# Baos_Board.net
KiCad netlist of a schematic drawn in EAGLE
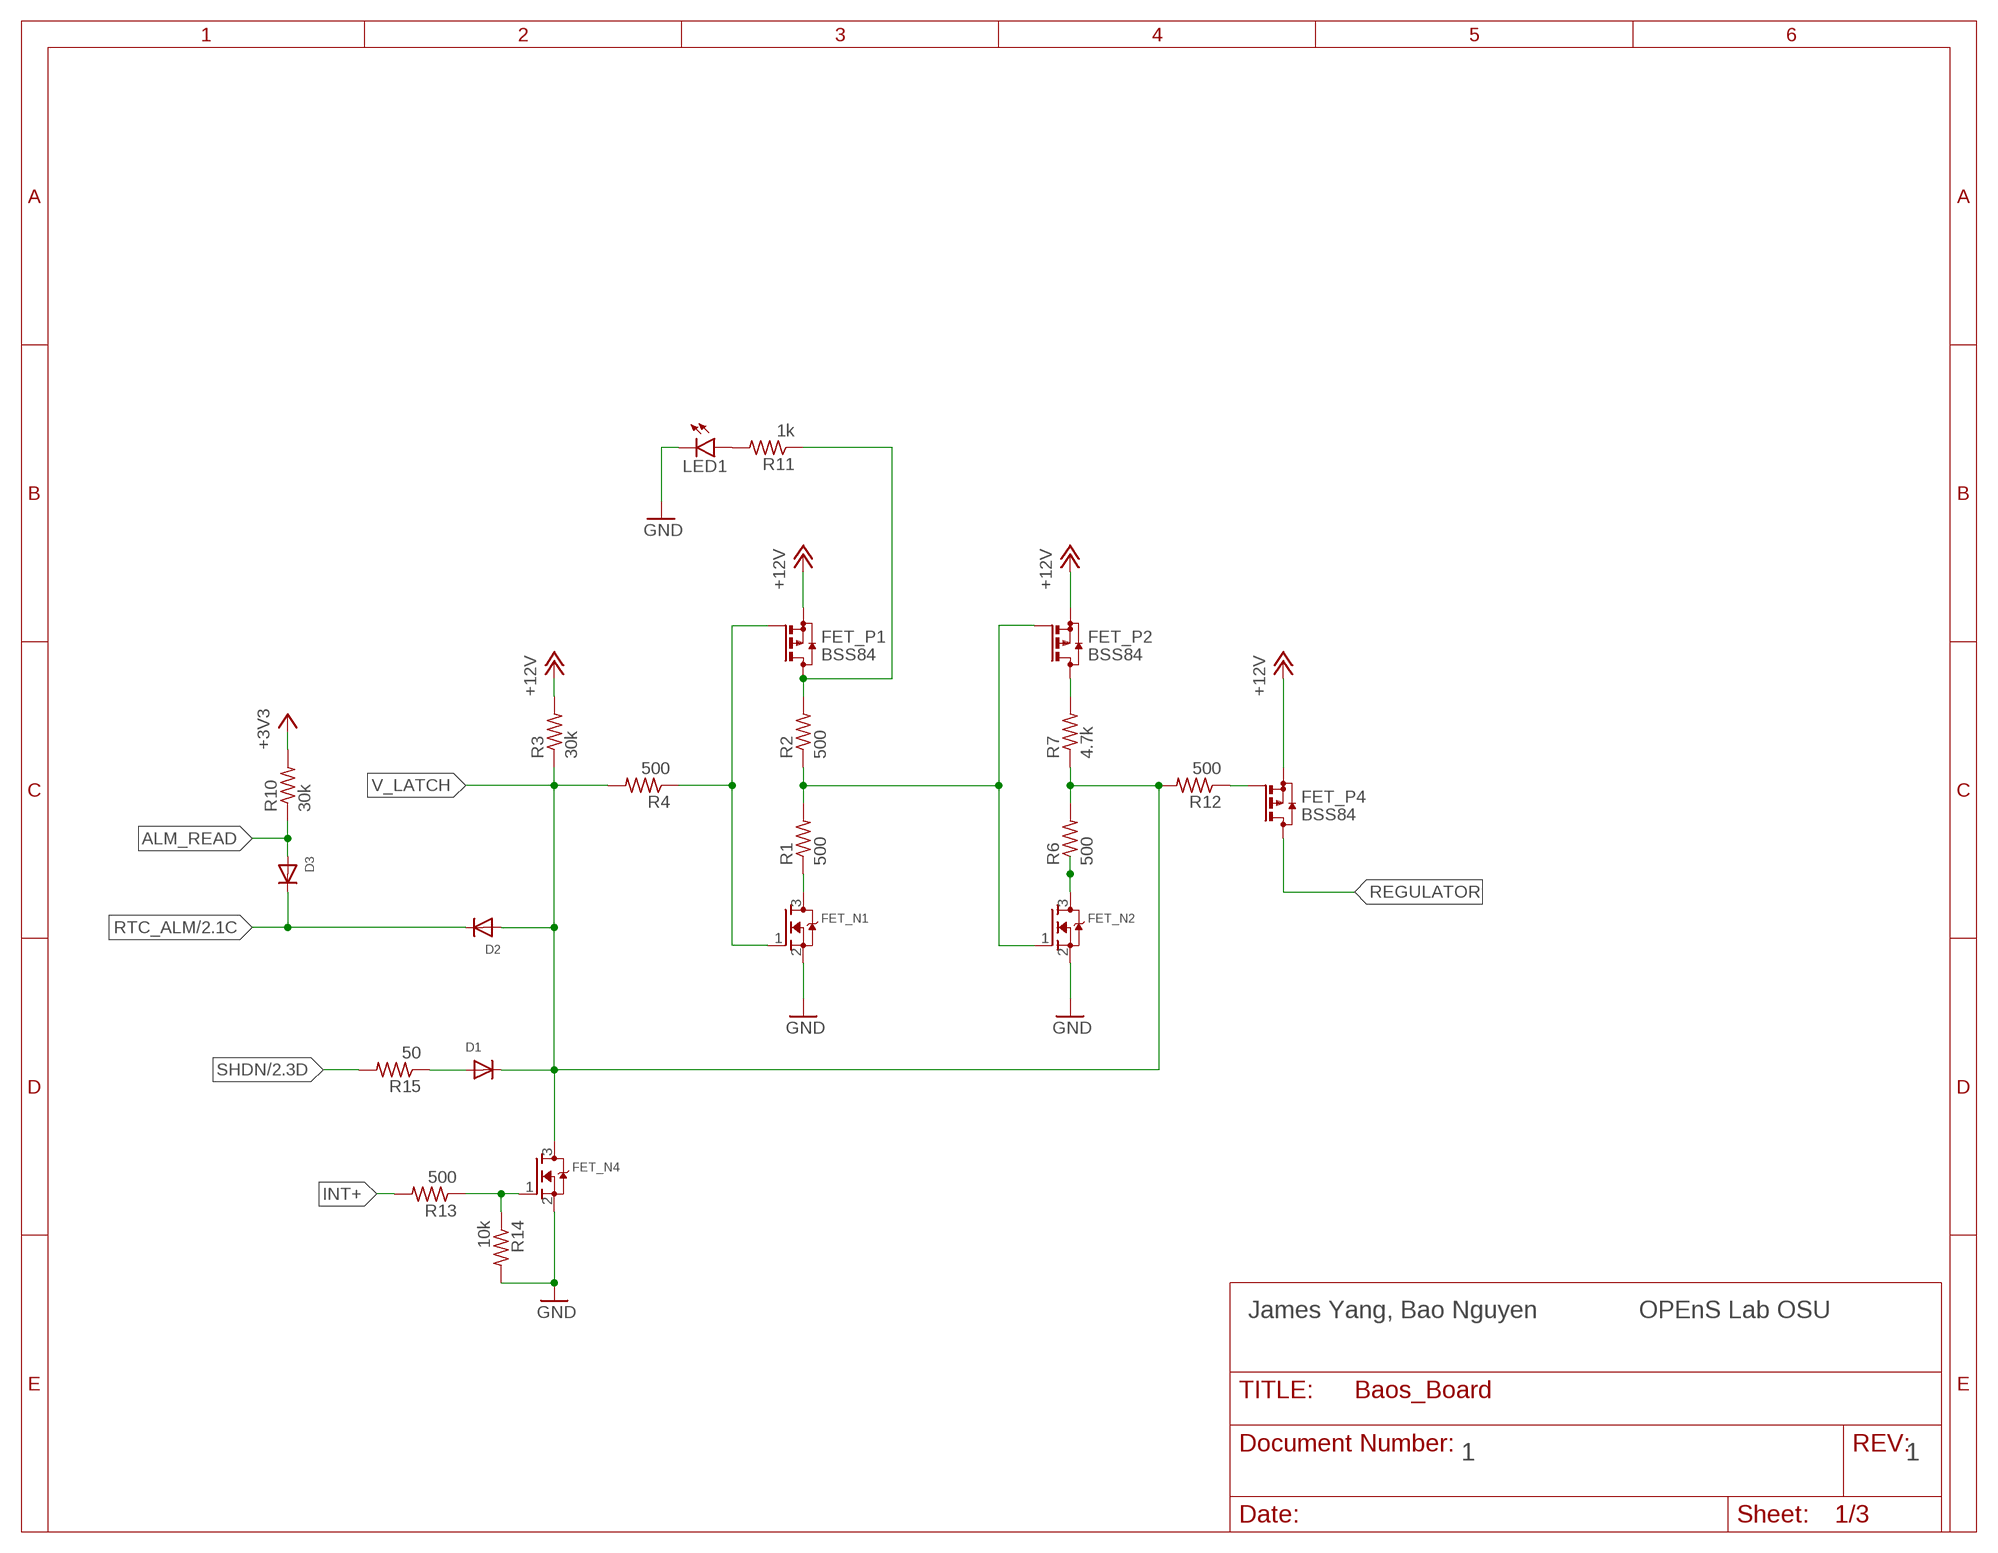
[diagram p0: schematic, sheet 1]
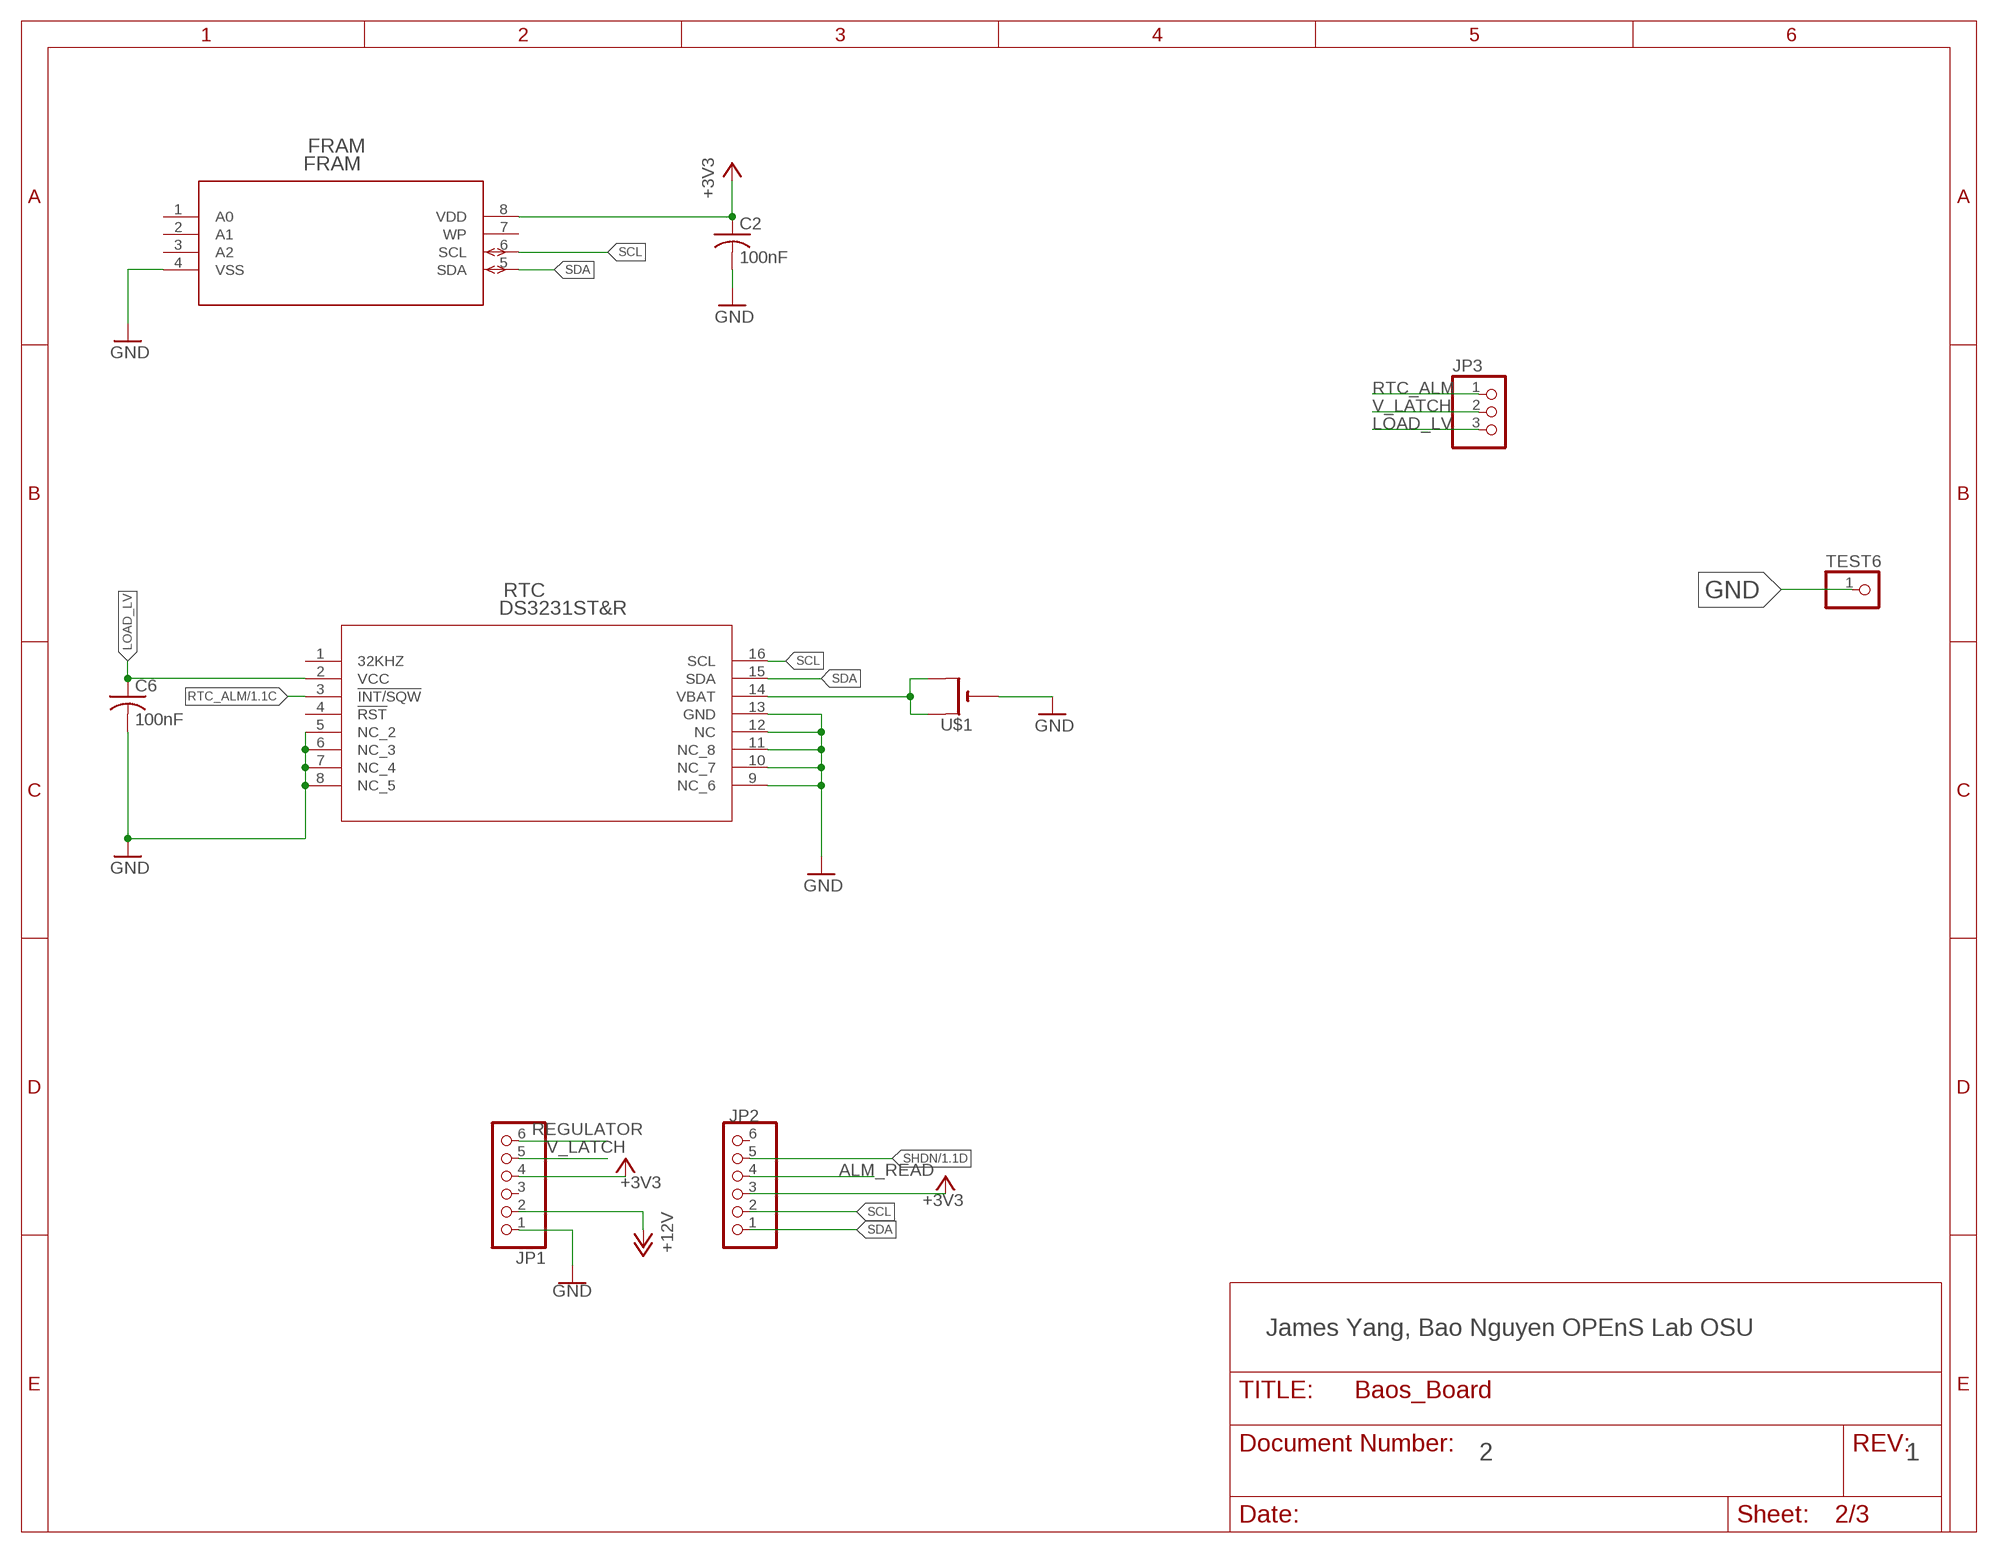
[diagram p1: schematic, sheet 2]

(export (version "E")
  (design (tool "Eeschema 10.0.6"))
  (components
    (comp (ref "D1")
      (value "DIODESOD-123")
      (footprint "eagle-import:SOD-123")
      (libsource (lib "eagle-import") (part "DIODESOD-123"))
    )
    (comp (ref "D2")
      (value "DIODESOD-123")
      (footprint "eagle-import:SOD-123")
      (libsource (lib "eagle-import") (part "DIODESOD-123"))
    )
    (comp (ref "D3")
      (value "DIODESOD-123")
      (footprint "eagle-import:SOD-123")
      (libsource (lib "eagle-import") (part "DIODESOD-123"))
    )
    (comp (ref "FET_N1")
      (value "MOSFET-NREFLOW")
      (footprint "eagle-import:SOT23")
      (libsource (lib "eagle-import") (part "MOSFET-NREFLOW"))
    )
    (comp (ref "FET_N2")
      (value "MOSFET-NREFLOW")
      (footprint "eagle-import:SOT23")
      (libsource (lib "eagle-import") (part "MOSFET-NREFLOW"))
    )
    (comp (ref "FET_N4")
      (value "MOSFET-NREFLOW")
      (footprint "eagle-import:SOT23")
      (libsource (lib "eagle-import") (part "MOSFET-NREFLOW"))
    )
    (comp (ref "FET_P1")
      (value "BSS84")
      (footprint "eagle-import:SOT23")
      (libsource (lib "eagle-import") (part "BSS84"))
    )
    (comp (ref "FET_P2")
      (value "BSS84")
      (footprint "eagle-import:SOT23")
      (libsource (lib "eagle-import") (part "BSS84"))
    )
    (comp (ref "FET_P4")
      (value "BSS84")
      (footprint "eagle-import:SOT23")
      (libsource (lib "eagle-import") (part "BSS84"))
    )
    (comp (ref "LED1")
      (value "LEDSMT1206")
      (footprint "eagle-import:1206")
      (libsource (lib "eagle-import") (part "LEDSMT1206"))
    )
    (comp (ref "R1")
      (value "500")
      (footprint "eagle-import:R0805")
      (libsource (lib "eagle-import") (part "R-US_R0805"))
    )
    (comp (ref "R2")
      (value "500")
      (footprint "eagle-import:R0805")
      (libsource (lib "eagle-import") (part "R-US_R0805"))
    )
    (comp (ref "R3")
      (value "30k")
      (footprint "eagle-import:R0805")
      (libsource (lib "eagle-import") (part "R-US_R0805"))
    )
    (comp (ref "R4")
      (value "500")
      (footprint "eagle-import:R0805")
      (libsource (lib "eagle-import") (part "R-US_R0805"))
    )
    (comp (ref "R6")
      (value "500")
      (footprint "eagle-import:R0805")
      (libsource (lib "eagle-import") (part "R-US_R0805"))
    )
    (comp (ref "R7")
      (value "4.7k")
      (footprint "eagle-import:R0805")
      (libsource (lib "eagle-import") (part "R-US_R0805"))
    )
    (comp (ref "R10")
      (value "30k")
      (footprint "eagle-import:R0805")
      (libsource (lib "eagle-import") (part "R-US_R0805"))
    )
    (comp (ref "R11")
      (value "1k")
      (footprint "eagle-import:R0805")
      (libsource (lib "eagle-import") (part "R-US_R0805"))
    )
    (comp (ref "R12")
      (value "500")
      (footprint "eagle-import:R0805")
      (libsource (lib "eagle-import") (part "R-US_R0805"))
    )
    (comp (ref "R13")
      (value "500")
      (footprint "eagle-import:R0805")
      (libsource (lib "eagle-import") (part "R-US_R0805"))
    )
    (comp (ref "R14")
      (value "10k")
      (footprint "eagle-import:R0805")
      (libsource (lib "eagle-import") (part "R-US_R0805"))
    )
    (comp (ref "R15")
      (value "50")
      (footprint "eagle-import:R0805")
      (libsource (lib "eagle-import") (part "R-US_R0805"))
    )
    (comp (ref "C2")
      (value "100nF")
      (footprint "eagle-import:C0805")
      (libsource (lib "eagle-import") (part "C-USC0805"))
    )
    (comp (ref "C6")
      (value "100nF")
      (footprint "eagle-import:C0805")
      (libsource (lib "eagle-import") (part "C-USC0805"))
    )
    (comp (ref "FRAM")
      (value "FRAM")
      (footprint "eagle-import:FPT-8P-M02")
      (fields (field (name "MANUFACTURER_PART_NUMBER") "Inc."))
      (libsource (lib "eagle-import") (part "FRAM"))
    )
    (comp (ref "JP1")
      (value "PINHD-1X6")
      (footprint "eagle-import:1X06")
      (libsource (lib "eagle-import") (part "PINHD-1X6"))
    )
    (comp (ref "JP2")
      (value "PINHD-1X6")
      (footprint "eagle-import:1X06")
      (libsource (lib "eagle-import") (part "PINHD-1X6"))
    )
    (comp (ref "JP3")
      (value "PINHD-1X3")
      (footprint "eagle-import:1X03")
      (libsource (lib "eagle-import") (part "PINHD-1X3"))
    )
    (comp (ref "RTC")
      (value "DS3231ST&R")
      (footprint "eagle-import:21-0042B_16")
      (fields (field (name "MANUFACTURER_PART_NUMBER") "DS3231S#T&R"))
      (libsource (lib "eagle-import") (part "DS3231ST&R"))
    )
    (comp (ref "TEST6")
      (value "PINHD-1X1")
      (footprint "eagle-import:1X01")
      (libsource (lib "eagle-import") (part "PINHD-1X1"))
    )
    (comp (ref "U$1")
      (value "CR1220SMT")
      (footprint "eagle-import:CR1220-SMD")
      (libsource (lib "eagle-import") (part "CR1220SMT"))
    )
  )
  (nets
    (net (code "1") (name "+3V3") (class "Default")
      (node (ref "C2") (pin "1") (pinfunction "1_1") (pintype "passive"))
      (node (ref "FRAM") (pin "8") (pinfunction "VDD_8") (pintype "power_in"))
      (node (ref "JP1") (pin "4") (pinfunction "4_4") (pintype "passive"))
      (node (ref "JP2") (pin "3") (pinfunction "3_3") (pintype "passive"))
      (node (ref "R10") (pin "2") (pinfunction "2_2") (pintype "passive"))
    )
    (net (code "2") (name "+12V") (class "Default")
      (node (ref "FET_P1") (pin "2") (pinfunction "S_2") (pintype "passive"))
      (node (ref "FET_P2") (pin "2") (pinfunction "S_2") (pintype "passive"))
      (node (ref "FET_P4") (pin "2") (pinfunction "S_2") (pintype "passive"))
      (node (ref "JP1") (pin "2") (pinfunction "2_2") (pintype "passive"))
      (node (ref "R3") (pin "2") (pinfunction "2_2") (pintype "passive"))
    )
    (net (code "3") (name "ALM_READ") (class "Default")
      (node (ref "D3") (pin "A") (pinfunction "A_A") (pintype "passive"))
      (node (ref "JP2") (pin "4") (pinfunction "4_4") (pintype "passive"))
      (node (ref "R10") (pin "1") (pinfunction "1_1") (pintype "passive"))
    )
    (net (code "4") (name "GND") (class "Default")
      (node (ref "C2") (pin "2") (pinfunction "2_2") (pintype "passive"))
      (node (ref "C6") (pin "2") (pinfunction "2_2") (pintype "passive"))
      (node (ref "FET_N1") (pin "2") (pinfunction "S_2") (pintype "bidirectional"))
      (node (ref "FET_N2") (pin "2") (pinfunction "S_2") (pintype "bidirectional"))
      (node (ref "FET_N4") (pin "2") (pinfunction "S_2") (pintype "bidirectional"))
      (node (ref "FRAM") (pin "4") (pinfunction "VSS_4") (pintype "power_in"))
      (node (ref "JP1") (pin "1") (pinfunction "1_1") (pintype "passive"))
      (node (ref "LED1") (pin "C") (pinfunction "C_C") (pintype "passive"))
      (node (ref "R14") (pin "2") (pinfunction "2_2") (pintype "passive"))
      (node (ref "RTC") (pin "10") (pinfunction "NC_7_10") (pintype "passive"))
      (node (ref "RTC") (pin "11") (pinfunction "NC_8_11") (pintype "passive"))
      (node (ref "RTC") (pin "12") (pinfunction "NC_12") (pintype "passive"))
      (node (ref "RTC") (pin "13") (pinfunction "GND_13") (pintype "power_in"))
      (node (ref "RTC") (pin "5") (pinfunction "NC_2_5") (pintype "passive"))
      (node (ref "RTC") (pin "6") (pinfunction "NC_3_6") (pintype "passive"))
      (node (ref "RTC") (pin "7") (pinfunction "NC_4_7") (pintype "passive"))
      (node (ref "RTC") (pin "8") (pinfunction "NC_5_8") (pintype "passive"))
      (node (ref "RTC") (pin "9") (pinfunction "NC_6_9") (pintype "passive"))
      (node (ref "TEST6") (pin "1") (pinfunction "1_1") (pintype "passive"))
      (node (ref "U$1") (pin "-") (pinfunction "-_-") (pintype "passive"))
    )
    (net (code "5") (name "INT+") (class "Default")
      (node (ref "R13") (pin "2") (pinfunction "2_2") (pintype "passive"))
    )
    (net (code "6") (name "LOAD_LV") (class "Default")
      (node (ref "C6") (pin "1") (pinfunction "1_1") (pintype "passive"))
      (node (ref "JP3") (pin "3") (pinfunction "3_3") (pintype "passive"))
      (node (ref "RTC") (pin "2") (pinfunction "VCC_2") (pintype "power_in"))
    )
    (net (code "7") (name "Net-(D1-PadA)") (class "Default")
      (node (ref "D1") (pin "A") (pinfunction "A_A") (pintype "passive"))
      (node (ref "R15") (pin "1") (pinfunction "1_1") (pintype "passive"))
    )
    (net (code "8") (name "Net-(FET_N1-D)") (class "Default")
      (node (ref "FET_N1") (pin "3") (pinfunction "D_3") (pintype "bidirectional"))
      (node (ref "R1") (pin "1") (pinfunction "1_1") (pintype "passive"))
    )
    (net (code "9") (name "Net-(FET_N1-G)") (class "Default")
      (node (ref "FET_N1") (pin "1") (pinfunction "G_1") (pintype "bidirectional"))
      (node (ref "FET_P1") (pin "1") (pinfunction "G_1") (pintype "passive"))
      (node (ref "R4") (pin "1") (pinfunction "1_1") (pintype "passive"))
    )
    (net (code "10") (name "Net-(FET_N2-D)") (class "Default")
      (node (ref "FET_N2") (pin "3") (pinfunction "D_3") (pintype "bidirectional"))
      (node (ref "R6") (pin "1") (pinfunction "1_1") (pintype "passive"))
    )
    (net (code "11") (name "Net-(FET_N2-G)") (class "Default")
      (node (ref "FET_N2") (pin "1") (pinfunction "G_1") (pintype "bidirectional"))
      (node (ref "FET_P2") (pin "1") (pinfunction "G_1") (pintype "passive"))
      (node (ref "R1") (pin "2") (pinfunction "2_2") (pintype "passive"))
      (node (ref "R2") (pin "1") (pinfunction "1_1") (pintype "passive"))
    )
    (net (code "12") (name "Net-(FET_N4-G)") (class "Default")
      (node (ref "FET_N4") (pin "1") (pinfunction "G_1") (pintype "bidirectional"))
      (node (ref "R13") (pin "1") (pinfunction "1_1") (pintype "passive"))
      (node (ref "R14") (pin "1") (pinfunction "1_1") (pintype "passive"))
    )
    (net (code "13") (name "Net-(FET_P1-D)") (class "Default")
      (node (ref "FET_P1") (pin "3") (pinfunction "D_3") (pintype "passive"))
      (node (ref "R11") (pin "1") (pinfunction "1_1") (pintype "passive"))
      (node (ref "R2") (pin "2") (pinfunction "2_2") (pintype "passive"))
    )
    (net (code "14") (name "Net-(FET_P2-D)") (class "Default")
      (node (ref "FET_P2") (pin "3") (pinfunction "D_3") (pintype "passive"))
      (node (ref "R7") (pin "2") (pinfunction "2_2") (pintype "passive"))
    )
    (net (code "15") (name "Net-(FET_P4-G)") (class "Default")
      (node (ref "FET_P4") (pin "1") (pinfunction "G_1") (pintype "passive"))
      (node (ref "R12") (pin "1") (pinfunction "1_1") (pintype "passive"))
    )
    (net (code "16") (name "Net-(LED1-PadA)") (class "Default")
      (node (ref "LED1") (pin "A") (pinfunction "A_A") (pintype "passive"))
      (node (ref "R11") (pin "2") (pinfunction "2_2") (pintype "passive"))
    )
    (net (code "17") (name "Net-(RTC-VBAT)") (class "Default")
      (node (ref "RTC") (pin "14") (pinfunction "VBAT_14") (pintype "power_in"))
      (node (ref "U$1") (pin "+$1") (pinfunction "+_+$1") (pintype "passive"))
      (node (ref "U$1") (pin "+$2") (pinfunction "+1_+$2") (pintype "passive"))
    )
    (net (code "18") (name "REGULATOR") (class "Default")
      (node (ref "FET_P4") (pin "3") (pinfunction "D_3") (pintype "passive"))
      (node (ref "JP1") (pin "6") (pinfunction "6_6") (pintype "passive"))
    )
    (net (code "19") (name "RTC_ALM") (class "Default")
      (node (ref "D2") (pin "C") (pinfunction "C_C") (pintype "passive"))
      (node (ref "D3") (pin "C") (pinfunction "C_C") (pintype "passive"))
      (node (ref "JP3") (pin "1") (pinfunction "1_1") (pintype "passive"))
      (node (ref "RTC") (pin "3") (pinfunction "~{INT/SQW}_3") (pintype "passive"))
    )
    (net (code "20") (name "SCL") (class "Default")
      (node (ref "FRAM") (pin "6") (pinfunction "SCL_6") (pintype "bidirectional"))
      (node (ref "JP2") (pin "2") (pinfunction "2_2") (pintype "passive"))
      (node (ref "RTC") (pin "16") (pinfunction "SCL_16") (pintype "passive"))
    )
    (net (code "21") (name "SDA") (class "Default")
      (node (ref "FRAM") (pin "5") (pinfunction "SDA_5") (pintype "bidirectional"))
      (node (ref "JP2") (pin "1") (pinfunction "1_1") (pintype "passive"))
      (node (ref "RTC") (pin "15") (pinfunction "SDA_15") (pintype "passive"))
    )
    (net (code "22") (name "SHDN") (class "Default")
      (node (ref "JP2") (pin "5") (pinfunction "5_5") (pintype "passive"))
      (node (ref "R15") (pin "2") (pinfunction "2_2") (pintype "passive"))
    )
    (net (code "23") (name "V_LATCH") (class "Default")
      (node (ref "D1") (pin "C") (pinfunction "C_C") (pintype "passive"))
      (node (ref "D2") (pin "A") (pinfunction "A_A") (pintype "passive"))
      (node (ref "FET_N4") (pin "3") (pinfunction "D_3") (pintype "bidirectional"))
      (node (ref "JP1") (pin "5") (pinfunction "5_5") (pintype "passive"))
      (node (ref "JP3") (pin "2") (pinfunction "2_2") (pintype "passive"))
      (node (ref "R12") (pin "2") (pinfunction "2_2") (pintype "passive"))
      (node (ref "R3") (pin "1") (pinfunction "1_1") (pintype "passive"))
      (node (ref "R4") (pin "2") (pinfunction "2_2") (pintype "passive"))
      (node (ref "R6") (pin "2") (pinfunction "2_2") (pintype "passive"))
      (node (ref "R7") (pin "1") (pinfunction "1_1") (pintype "passive"))
    )
    (net (code "24") (name "unconnected-(FRAM-A0-Pad1)") (class "Default")
      (node (ref "FRAM") (pin "1") (pinfunction "A0_1") (pintype "passive"))
    )
    (net (code "25") (name "unconnected-(FRAM-A1-Pad2)") (class "Default")
      (node (ref "FRAM") (pin "2") (pinfunction "A1_2") (pintype "passive"))
    )
    (net (code "26") (name "unconnected-(FRAM-A2-Pad3)") (class "Default")
      (node (ref "FRAM") (pin "3") (pinfunction "A2_3") (pintype "passive"))
    )
    (net (code "27") (name "unconnected-(FRAM-WP-Pad7)") (class "Default")
      (node (ref "FRAM") (pin "7") (pinfunction "WP_7") (pintype "passive"))
    )
    (net (code "28") (name "unconnected-(JP1-Pad3)") (class "Default")
      (node (ref "JP1") (pin "3") (pinfunction "3_3") (pintype "passive"))
    )
    (net (code "29") (name "unconnected-(JP2-Pad6)") (class "Default")
      (node (ref "JP2") (pin "6") (pinfunction "6_6") (pintype "passive"))
    )
    (net (code "30") (name "unconnected-(RTC-32KHZ-Pad1)") (class "Default")
      (node (ref "RTC") (pin "1") (pinfunction "32KHZ_1") (pintype "passive"))
    )
    (net (code "31") (name "unconnected-(RTC-~{RST}-Pad4)") (class "Default")
      (node (ref "RTC") (pin "4") (pinfunction "~{RST}_4") (pintype "passive"))
    )
  )
)
